# demo1.net
KiCad netlist of a schematic drawn in EAGLE
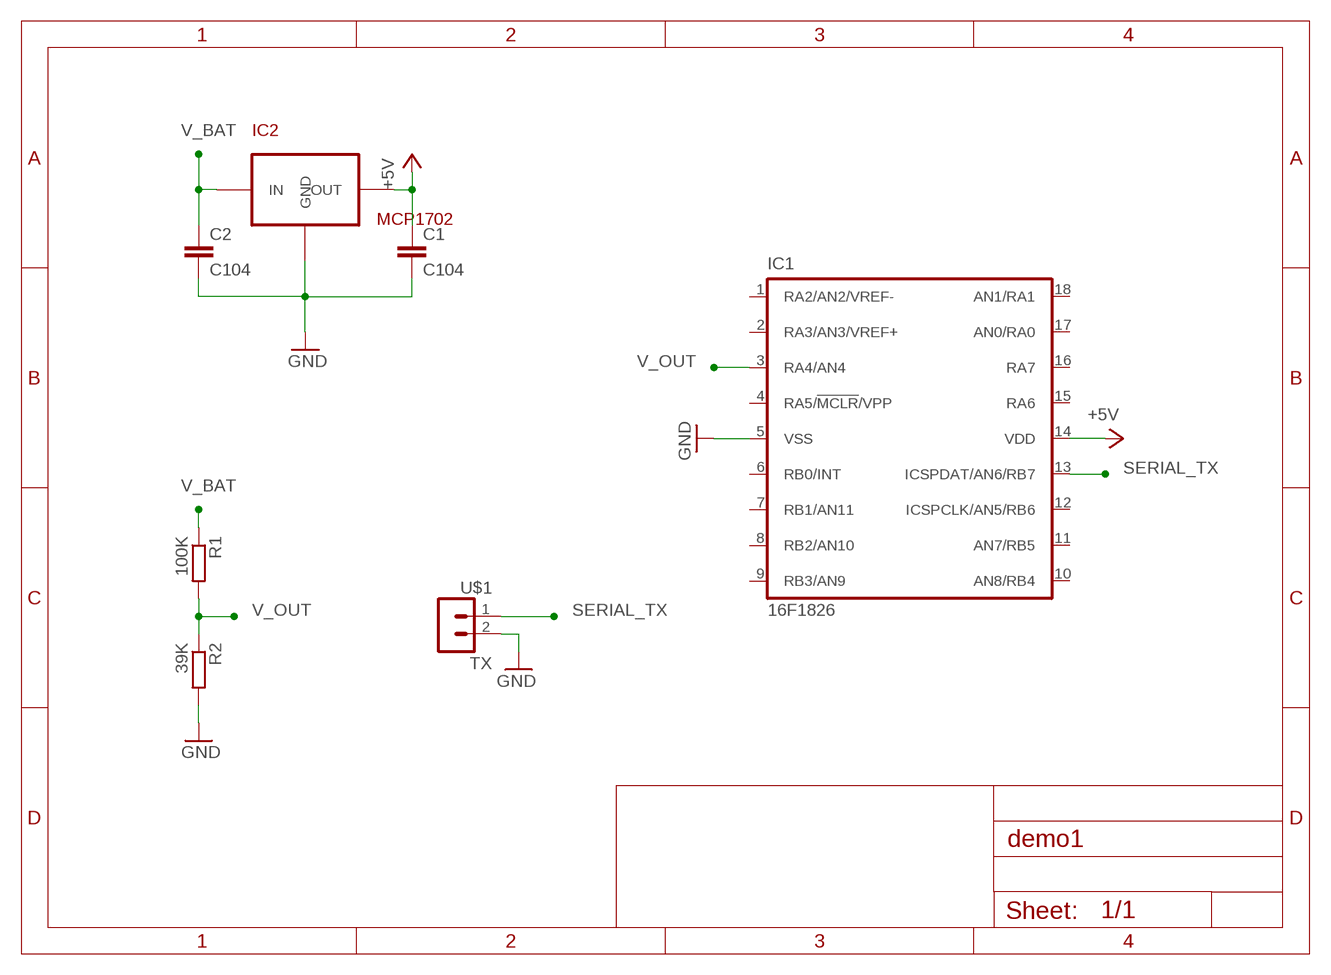
[diagram p0: schematic, sheet 1]

(export (version "E")
  (design (tool "Eeschema 10.0.6"))
  (components
    (comp (ref "C1")
      (value "C104")
      (footprint "eagle-import:0805")
      (libsource (lib "eagle-import") (part "COND_SMD0805"))
    )
    (comp (ref "C2")
      (value "C104")
      (footprint "eagle-import:0805")
      (libsource (lib "eagle-import") (part "COND_SMD0805"))
    )
    (comp (ref "IC1")
      (value "16F1826")
      (footprint "eagle-import:SO-18W")
      (libsource (lib "eagle-import") (part "PIC16F1826-SO"))
    )
    (comp (ref "IC2")
      (value "MCP1702")
      (footprint "eagle-import:SOT-89")
      (libsource (lib "eagle-import") (part "MCP1700SOT89"))
    )
    (comp (ref "R1")
      (value "100K")
      (footprint "eagle-import:0805")
      (libsource (lib "eagle-import") (part "RES_SMD-0805"))
    )
    (comp (ref "R2")
      (value "39K")
      (footprint "eagle-import:0805")
      (libsource (lib "eagle-import") (part "RES_SMD-0805"))
    )
    (comp (ref "U$1")
      (value "TX")
      (footprint "eagle-import:PINHEAD-MALE-2H-LOCK")
      (libsource (lib "eagle-import") (part "CON-2PH-LOCK"))
    )
  )
  (nets
    (net (code "1") (name "+5V") (class "Default")
      (node (ref "C1") (pin "1") (pinfunction "1_1") (pintype "passive"))
      (node (ref "IC1") (pin "14") (pinfunction "VDD_14") (pintype "power_in"))
      (node (ref "IC2") (pin "3") (pinfunction "OUT_3") (pintype "power_in"))
    )
    (net (code "2") (name "/SERIAL_TX") (class "Default")
      (node (ref "IC1") (pin "13") (pinfunction "ICSPDAT/AN6/RB7_13") (pintype "bidirectional"))
      (node (ref "U$1") (pin "1") (pinfunction "1_1") (pintype "passive"))
    )
    (net (code "3") (name "/V_BAT") (class "Default")
      (node (ref "C2") (pin "1") (pinfunction "1_1") (pintype "passive"))
      (node (ref "IC2") (pin "2") (pinfunction "IN_2") (pintype "power_in"))
      (node (ref "R1") (pin "1") (pinfunction "1_1") (pintype "passive"))
    )
    (net (code "4") (name "/V_OUT") (class "Default")
      (node (ref "IC1") (pin "3") (pinfunction "RA4/AN4_3") (pintype "bidirectional"))
      (node (ref "R1") (pin "2") (pinfunction "2_2") (pintype "passive"))
      (node (ref "R2") (pin "1") (pinfunction "1_1") (pintype "passive"))
    )
    (net (code "5") (name "GND") (class "Default")
      (node (ref "C1") (pin "2") (pinfunction "2_2") (pintype "passive"))
      (node (ref "C2") (pin "2") (pinfunction "2_2") (pintype "passive"))
      (node (ref "IC1") (pin "5") (pinfunction "VSS_5") (pintype "power_in"))
      (node (ref "IC2") (pin "1") (pinfunction "GND_1") (pintype "power_in"))
      (node (ref "R2") (pin "2") (pinfunction "2_2") (pintype "passive"))
      (node (ref "U$1") (pin "2") (pinfunction "2_2") (pintype "passive"))
    )
    (net (code "6") (name "unconnected-(IC1-AN0{slash}RA0-Pad17)") (class "Default")
      (node (ref "IC1") (pin "17") (pinfunction "AN0/RA0_17") (pintype "bidirectional"))
    )
    (net (code "7") (name "unconnected-(IC1-AN1{slash}RA1-Pad18)") (class "Default")
      (node (ref "IC1") (pin "18") (pinfunction "AN1/RA1_18") (pintype "bidirectional"))
    )
    (net (code "8") (name "unconnected-(IC1-AN7{slash}RB5-Pad11)") (class "Default")
      (node (ref "IC1") (pin "11") (pinfunction "AN7/RB5_11") (pintype "bidirectional"))
    )
    (net (code "9") (name "unconnected-(IC1-AN8{slash}RB4-Pad10)") (class "Default")
      (node (ref "IC1") (pin "10") (pinfunction "AN8/RB4_10") (pintype "bidirectional"))
    )
    (net (code "10") (name "unconnected-(IC1-ICSPCLK{slash}AN5{slash}RB6-Pad12)") (class "Default")
      (node (ref "IC1") (pin "12") (pinfunction "ICSPCLK/AN5/RB6_12") (pintype "bidirectional"))
    )
    (net (code "11") (name "unconnected-(IC1-RA2{slash}AN2{slash}VREF--Pad1)") (class "Default")
      (node (ref "IC1") (pin "1") (pinfunction "RA2/AN2/VREF-_1") (pintype "bidirectional"))
    )
    (net (code "12") (name "unconnected-(IC1-RA3{slash}AN3{slash}VREF+-Pad2)") (class "Default")
      (node (ref "IC1") (pin "2") (pinfunction "RA3/AN3/VREF+_2") (pintype "bidirectional"))
    )
    (net (code "13") (name "unconnected-(IC1-RA5{slash}~{MCLR}{slash}VPP-Pad4)") (class "Default")
      (node (ref "IC1") (pin "4") (pinfunction "RA5/~{MCLR}/VPP_4") (pintype "bidirectional"))
    )
    (net (code "14") (name "unconnected-(IC1-RA6-Pad15)") (class "Default")
      (node (ref "IC1") (pin "15") (pinfunction "RA6_15") (pintype "bidirectional"))
    )
    (net (code "15") (name "unconnected-(IC1-RA7-Pad16)") (class "Default")
      (node (ref "IC1") (pin "16") (pinfunction "RA7_16") (pintype "bidirectional"))
    )
    (net (code "16") (name "unconnected-(IC1-RB0{slash}INT-Pad6)") (class "Default")
      (node (ref "IC1") (pin "6") (pinfunction "RB0/INT_6") (pintype "bidirectional"))
    )
    (net (code "17") (name "unconnected-(IC1-RB1{slash}AN11-Pad7)") (class "Default")
      (node (ref "IC1") (pin "7") (pinfunction "RB1/AN11_7") (pintype "bidirectional"))
    )
    (net (code "18") (name "unconnected-(IC1-RB2{slash}AN10-Pad8)") (class "Default")
      (node (ref "IC1") (pin "8") (pinfunction "RB2/AN10_8") (pintype "bidirectional"))
    )
    (net (code "19") (name "unconnected-(IC1-RB3{slash}AN9-Pad9)") (class "Default")
      (node (ref "IC1") (pin "9") (pinfunction "RB3/AN9_9") (pintype "bidirectional"))
    )
  )
)
